# VC_Interface.net
KiCad netlist of a schematic drawn in Altium Designer
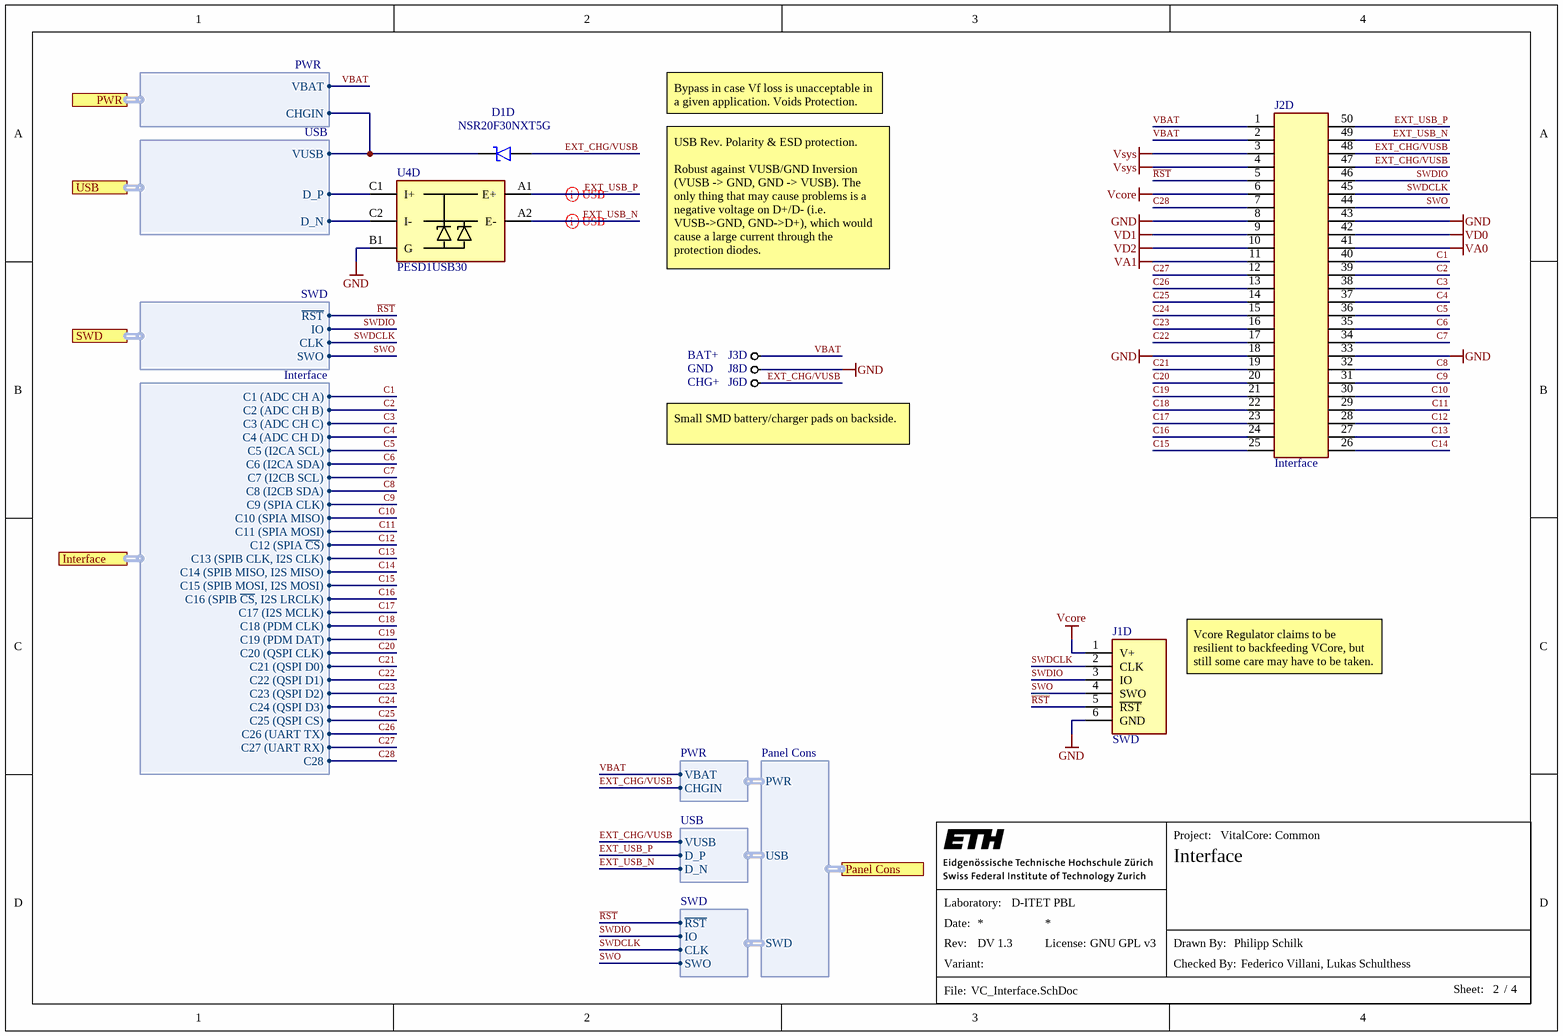
[diagram p0: VC_Interface.SchDoc]

(export (version "E")
  (design (tool "Eeschema 10.0.6"))
  (components
    (comp (ref "D1D")
      (value "NSR20F30NXT5G")
      (footprint "VC_PCBLib:DSN2_ONSemi")
      (description "Small Signal Schottky Diode, 30 V, 2 A")
      (fields (field (name "MANUFACTURER") "ON Semiconductor"))
      (libsource (lib "VC_SchematicLib") (part "D_NSR20F30NXT5G"))
    )
    (comp (ref "J1D")
      (value "SWD")
      (footprint "VC_PCBLib:CONN_SWD_PADS_P1.27mm")
      (description "SWD Pogo Pads")
      (libsource (lib "VC_SchematicLib") (part "CONN_SWD_PADS"))
    )
    (comp (ref "J2D")
      (value "Interface")
      (footprint "VC_PCBLib:CONN_COMBI_50P")
      (libsource (lib "VC_SchematicLib") (part "CONN_50P_M_COMBI_INTERFACE"))
    )
    (comp (ref "J3D")
      (value "BAT+")
      (footprint "VC_PCBLib:PADSMD_ROUND")
      (description "SMD Pad")
      (libsource (lib "VC_SchematicLib") (part "PADSMD"))
    )
    (comp (ref "J6D")
      (value "CHG+")
      (footprint "VC_PCBLib:PADSMD_ROUND")
      (description "SMD Pad")
      (libsource (lib "VC_SchematicLib") (part "PADSMD"))
    )
    (comp (ref "J8D")
      (value "GND")
      (footprint "VC_PCBLib:PADSMD_ROUND")
      (description "SMD Pad")
      (libsource (lib "VC_SchematicLib") (part "PADSMD"))
    )
    (comp (ref "U4D")
      (value "PESD1USB30")
      (footprint "VC_PCBLib:WLCSP_5_2-1-2_P0.4")
      (description "ESD Suppressor Diode TVS Uni-Dir 5V 5-Pin WLCSP T/R")
      (fields (field (name "MANUFACTURER") "NXP Semiconductors"))
      (libsource (lib "VC_SchematicLib") (part "PESD1USB30"))
    )
  )
  (nets
    (net (code "5") (name "/C1") (class "Default") (node (ref "J2D") (pin "40") (pintype "passive")))
    (net (code "6") (name "/C2") (class "Default") (node (ref "J2D") (pin "39") (pintype "passive")))
    (net (code "7") (name "/C3") (class "Default") (node (ref "J2D") (pin "38") (pintype "passive")))
    (net (code "8") (name "/C4") (class "Default") (node (ref "J2D") (pin "37") (pintype "passive")))
    (net (code "9") (name "/C5") (class "Default") (node (ref "J2D") (pin "36") (pintype "passive")))
    (net (code "10") (name "/C6") (class "Default") (node (ref "J2D") (pin "35") (pintype "passive")))
    (net (code "11") (name "/C7") (class "Default") (node (ref "J2D") (pin "34") (pintype "passive")))
    (net (code "12") (name "/C8") (class "Default") (node (ref "J2D") (pin "32") (pintype "passive")))
    (net (code "13") (name "/C9") (class "Default") (node (ref "J2D") (pin "31") (pintype "passive")))
    (net (code "14") (name "/C10") (class "Default") (node (ref "J2D") (pin "30") (pintype "passive")))
    (net (code "15") (name "/C11") (class "Default") (node (ref "J2D") (pin "29") (pintype "passive")))
    (net (code "16") (name "/C12") (class "Default") (node (ref "J2D") (pin "28") (pintype "passive")))
    (net (code "17") (name "/C13") (class "Default") (node (ref "J2D") (pin "27") (pintype "passive")))
    (net (code "18") (name "/C14") (class "Default") (node (ref "J2D") (pin "26") (pintype "passive")))
    (net (code "19") (name "/C15") (class "Default") (node (ref "J2D") (pin "25") (pintype "passive")))
    (net (code "20") (name "/C16") (class "Default") (node (ref "J2D") (pin "24") (pintype "passive")))
    (net (code "21") (name "/C17") (class "Default") (node (ref "J2D") (pin "23") (pintype "passive")))
    (net (code "22") (name "/C18") (class "Default") (node (ref "J2D") (pin "22") (pintype "passive")))
    (net (code "23") (name "/C19") (class "Default") (node (ref "J2D") (pin "21") (pintype "passive")))
    (net (code "24") (name "/C20") (class "Default") (node (ref "J2D") (pin "20") (pintype "passive")))
    (net (code "25") (name "/C21") (class "Default") (node (ref "J2D") (pin "19") (pintype "passive")))
    (net (code "26") (name "/C22") (class "Default") (node (ref "J2D") (pin "17") (pintype "passive")))
    (net (code "27") (name "/C23") (class "Default") (node (ref "J2D") (pin "16") (pintype "passive")))
    (net (code "28") (name "/C24") (class "Default") (node (ref "J2D") (pin "15") (pintype "passive")))
    (net (code "29") (name "/C25") (class "Default") (node (ref "J2D") (pin "14") (pintype "passive")))
    (net (code "30") (name "/C26") (class "Default") (node (ref "J2D") (pin "13") (pintype "passive")))
    (net (code "31") (name "/C27") (class "Default") (node (ref "J2D") (pin "12") (pintype "passive")))
    (net (code "32") (name "/C28") (class "Default") (node (ref "J2D") (pin "7") (pintype "passive")))
    (net (code "33") (name "/EXT_CHG{slash}VUSB") (class "Default")
      (node (ref "D1D") (pin "2") (pinfunction "Anode_2") (pintype "passive"))
      (node (ref "J2D") (pin "47") (pintype "passive"))
      (node (ref "J2D") (pin "48") (pintype "passive"))
      (node (ref "J6D") (pin "0") (pintype "passive"))
    )
    (net (code "34") (name "/EXT_USB_N") (class "Default")
      (node (ref "J2D") (pin "49") (pintype "passive"))
      (node (ref "U4D") (pin "A2") (pinfunction "E-_A2") (pintype "passive"))
    )
    (net (code "35") (name "/EXT_USB_P") (class "Default")
      (node (ref "J2D") (pin "50") (pintype "passive"))
      (node (ref "U4D") (pin "A1") (pinfunction "E+_A1") (pintype "passive"))
    )
    (net (code "37") (name "/SWDCLK") (class "Default")
      (node (ref "J1D") (pin "2") (pinfunction "CLK_2") (pintype "passive"))
      (node (ref "J2D") (pin "45") (pintype "passive"))
    )
    (net (code "38") (name "/SWDIO") (class "Default")
      (node (ref "J1D") (pin "3") (pinfunction "IO_3") (pintype "passive"))
      (node (ref "J2D") (pin "46") (pintype "passive"))
    )
    (net (code "39") (name "/SWO") (class "Default")
      (node (ref "J1D") (pin "4") (pinfunction "SWO_4") (pintype "passive"))
      (node (ref "J2D") (pin "44") (pintype "passive"))
    )
    (net (code "40") (name "/VBAT") (class "Default")
      (node (ref "J2D") (pin "1") (pintype "passive"))
      (node (ref "J2D") (pin "2") (pintype "passive"))
      (node (ref "J3D") (pin "0") (pintype "passive"))
    )
    (net (code "45") (name "/~{RST}") (class "Default")
      (node (ref "J1D") (pin "5") (pinfunction "~{RST}_5") (pintype "passive"))
      (node (ref "J2D") (pin "5") (pintype "passive"))
    )
    (net (code "46") (name "GND") (class "Default")
      (node (ref "J1D") (pin "6") (pinfunction "GND_6") (pintype "passive"))
      (node (ref "J2D") (pin "18") (pintype "passive"))
      (node (ref "J2D") (pin "33") (pintype "passive"))
      (node (ref "J2D") (pin "43") (pintype "passive"))
      (node (ref "J2D") (pin "8") (pintype "passive"))
      (node (ref "J8D") (pin "0") (pintype "passive"))
      (node (ref "U4D") (pin "B1") (pinfunction "G_B1") (pintype "passive"))
    )
    (net (code "47") (name "VA0") (class "Default") (node (ref "J2D") (pin "41") (pintype "passive")))
    (net (code "48") (name "VA1") (class "Default") (node (ref "J2D") (pin "11") (pintype "passive")))
    (net (code "49") (name "VD0") (class "Default") (node (ref "J2D") (pin "42") (pintype "passive")))
    (net (code "50") (name "VD1") (class "Default") (node (ref "J2D") (pin "9") (pintype "passive")))
    (net (code "51") (name "VD2") (class "Default") (node (ref "J2D") (pin "10") (pintype "passive")))
    (net (code "52") (name "Vcore") (class "Default")
      (node (ref "J1D") (pin "1") (pinfunction "V+_1") (pintype "passive"))
      (node (ref "J2D") (pin "6") (pintype "passive"))
    )
    (net (code "53") (name "Vsys") (class "Default")
      (node (ref "J2D") (pin "3") (pintype "passive"))
      (node (ref "J2D") (pin "4") (pintype "passive"))
    )
    (net (code "54") (name "unconnected-(D1D-Cathode-Pad1)") (class "Default")
      (node (ref "D1D") (pin "1") (pinfunction "Cathode_1") (pintype "passive"))
    )
    (net (code "55") (name "unconnected-(U4D-I+-PadC1)") (class "Default")
      (node (ref "U4D") (pin "C1") (pinfunction "I+_C1") (pintype "passive"))
    )
    (net (code "56") (name "unconnected-(U4D-I--PadC2)") (class "Default")
      (node (ref "U4D") (pin "C2") (pinfunction "I-_C2") (pintype "passive"))
    )
  )
)
